# SCH_d_02_e_01.net
KiCad netlist of a schematic drawn in EasyEDA
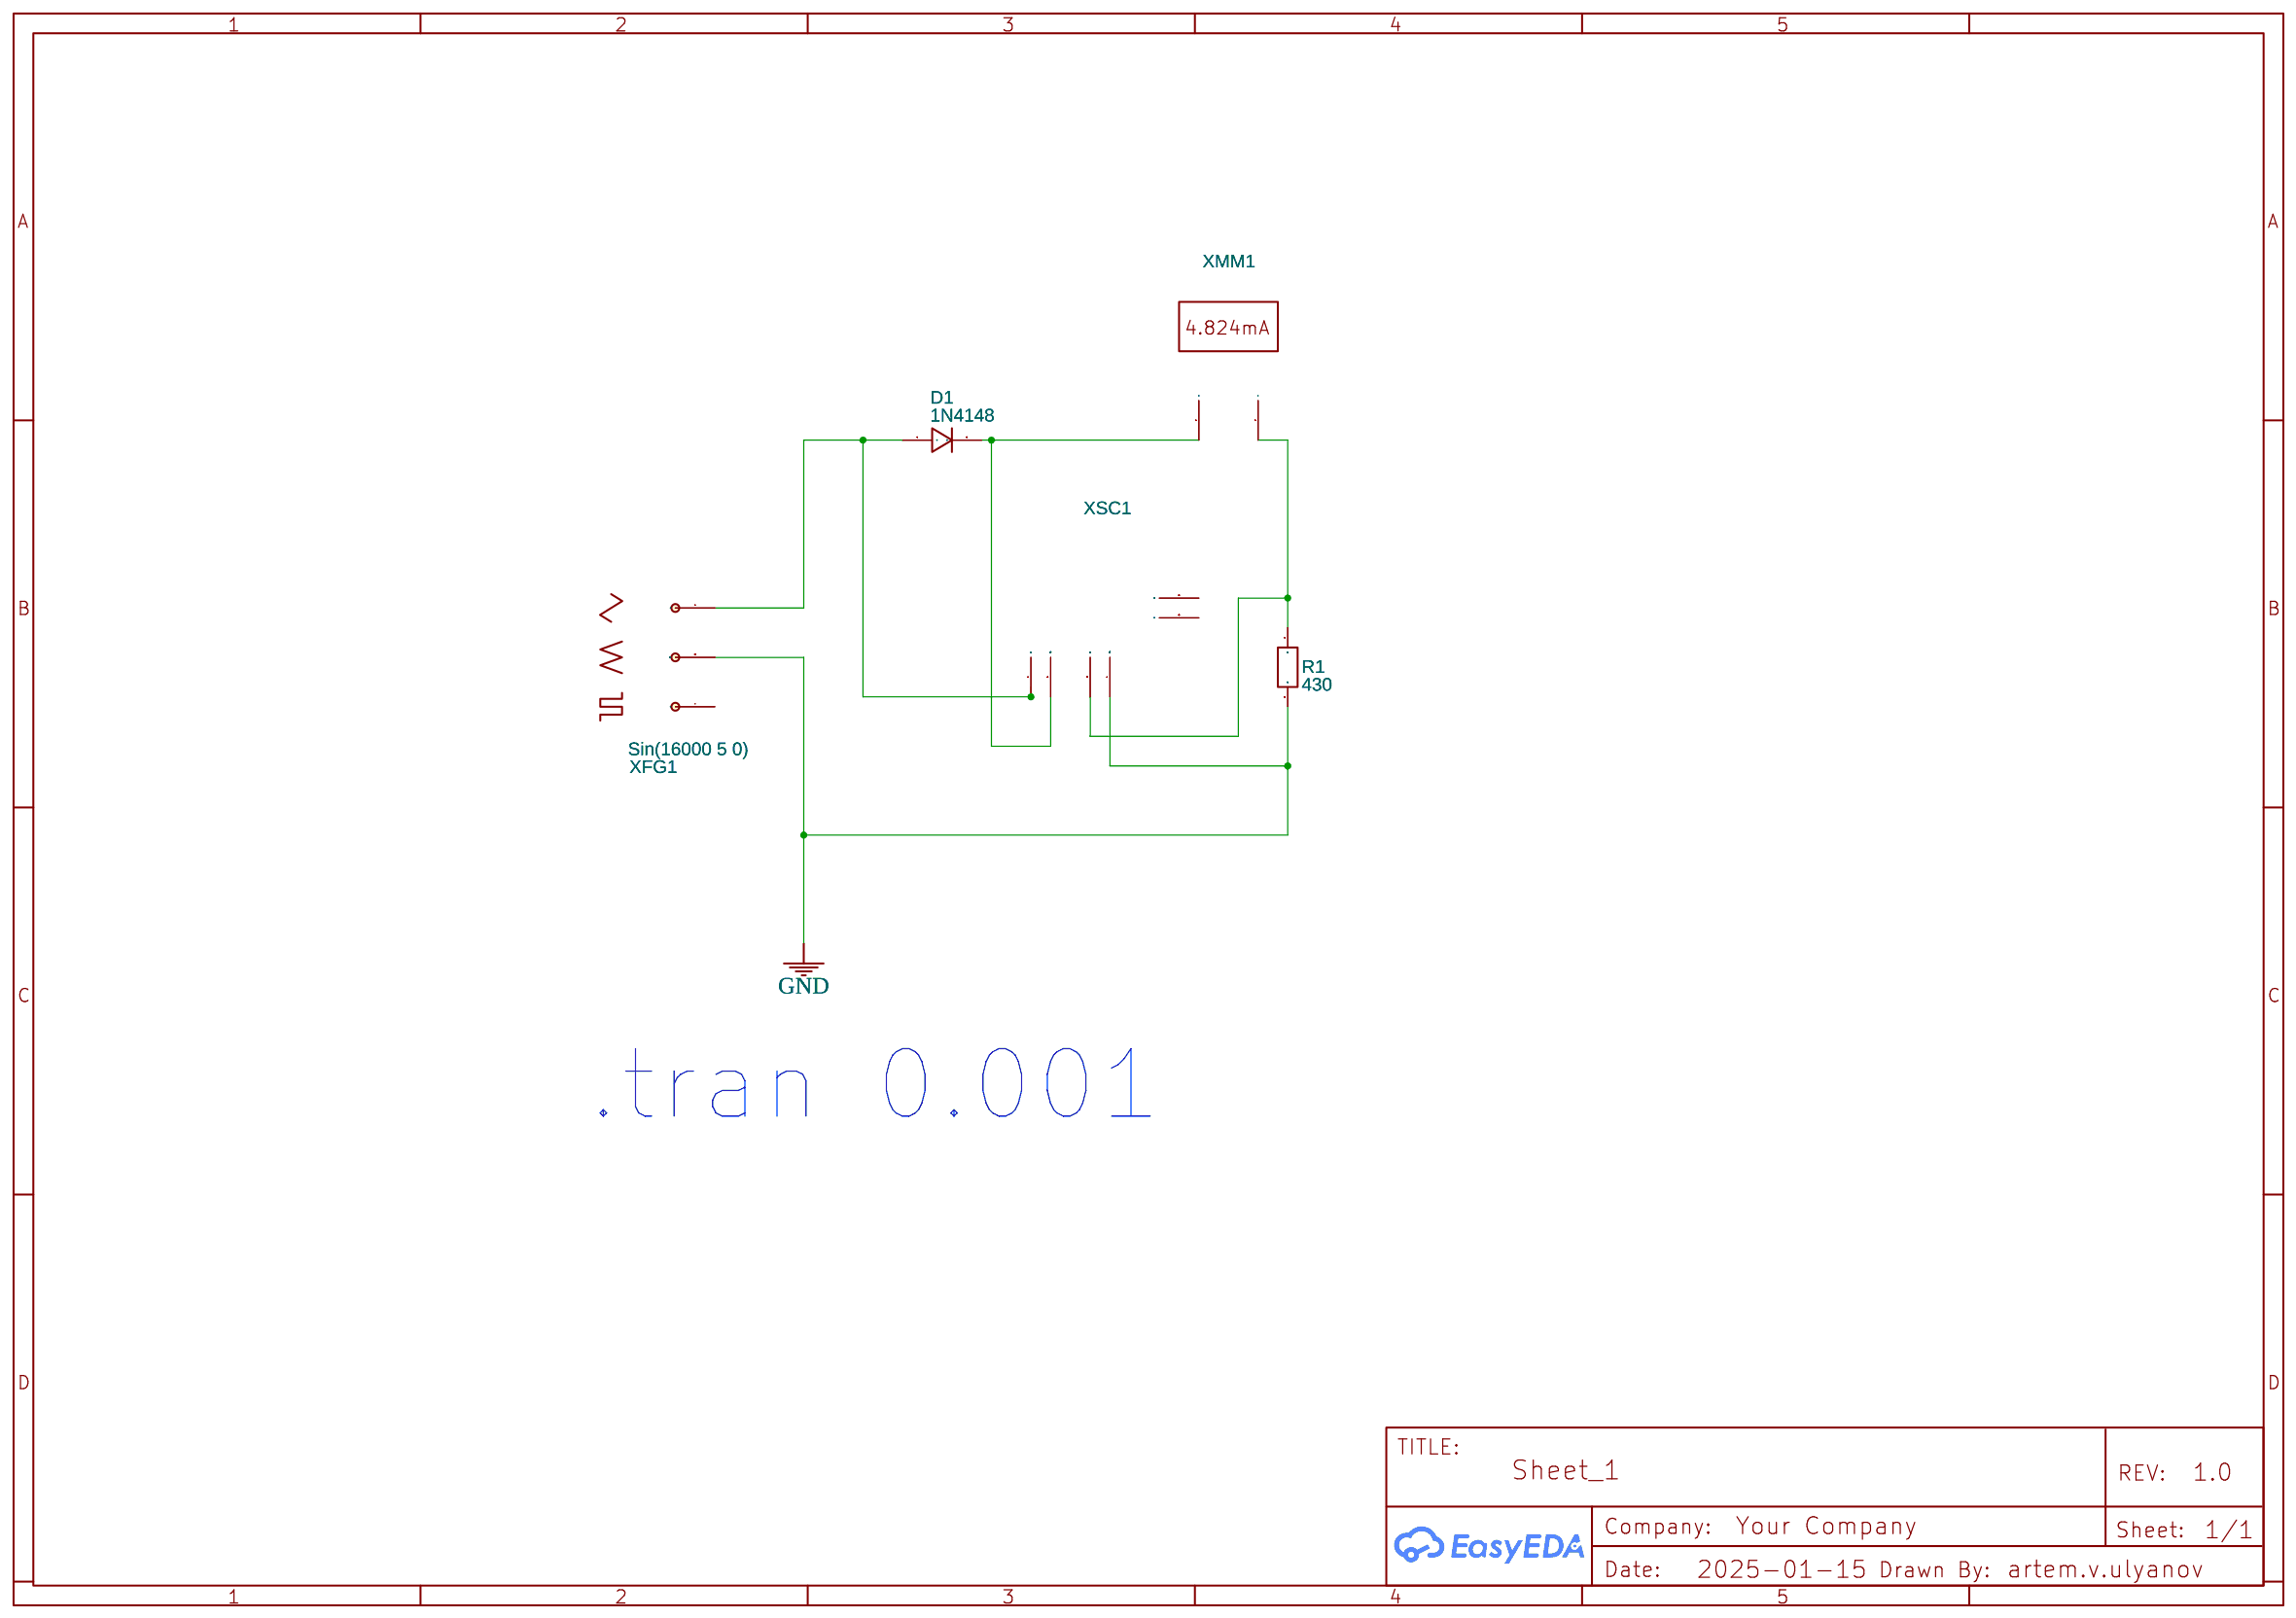
[diagram p0: schematic sheet]

(export (version "E")
  (design (tool "Eeschema 10.0.6"))
  (components
    (comp (ref "D1") (value "1N4148") (libsource (lib "") (part "1N4148")))
    (comp (ref "R1") (value "430") (libsource (lib "") (part "R_0603_EU")))
    (comp (ref "XFG1") (value "Sin(16000 5 0)") (libsource (lib "") (part "FUNCTIONGENERATOR")))
    (comp (ref "XMM1") (value "Multimeter") (libsource (lib "") (part "MULTIMETER")))
    (comp (ref "XSC1") (value "Oscilloscope") (libsource (lib "") (part "OSCILLOSCOPE")))
  )
  (nets
    (net (code "1") (name "GND") (class "Default")
      (node (ref "R1") (pin "2") (pinfunction "2_2") (pintype "unspecified"))
      (node (ref "XFG1") (pin "COM") (pinfunction "COM_COM") (pintype "unspecified"))
      (node (ref "XSC1") (pin "4") (pinfunction "GND2_4") (pintype "unspecified"))
    )
    (net (code "2") (name "Net-(D1-A)") (class "Default")
      (node (ref "D1") (pin "1") (pinfunction "A_1") (pintype "unspecified"))
      (node (ref "XFG1") (pin "+") (pinfunction "+_+") (pintype "unspecified"))
      (node (ref "XSC1") (pin "1") (pinfunction "A_1") (pintype "unspecified"))
    )
    (net (code "3") (name "Net-(D1-K)") (class "Default")
      (node (ref "D1") (pin "2") (pinfunction "K_2") (pintype "unspecified"))
      (node (ref "XMM1") (pin "1") (pinfunction "+_1") (pintype "unspecified"))
      (node (ref "XSC1") (pin "2") (pinfunction "GND1_2") (pintype "unspecified"))
    )
    (net (code "4") (name "Net-(XMM1-I)") (class "Default")
      (node (ref "R1") (pin "1") (pinfunction "1_1") (pintype "unspecified"))
      (node (ref "XMM1") (pin "2") (pinfunction "I_2") (pintype "unspecified"))
      (node (ref "XSC1") (pin "3") (pinfunction "B_3") (pintype "unspecified"))
    )
    (net (code "5") (name "unconnected-(XFG1-Pad-)") (class "Default")
      (node (ref "XFG1") (pin "-") (pinfunction "-_-") (pintype "unspecified"))
    )
    (net (code "6") (name "unconnected-(XSC1-T+-Pad5)") (class "Default")
      (node (ref "XSC1") (pin "5") (pinfunction "T+_5") (pintype "unspecified"))
    )
    (net (code "7") (name "unconnected-(XSC1-T--Pad6)") (class "Default")
      (node (ref "XSC1") (pin "6") (pinfunction "T-_6") (pintype "unspecified"))
    )
  )
)
